# tiny433mhz.net
KiCad netlist of a schematic drawn in EAGLE
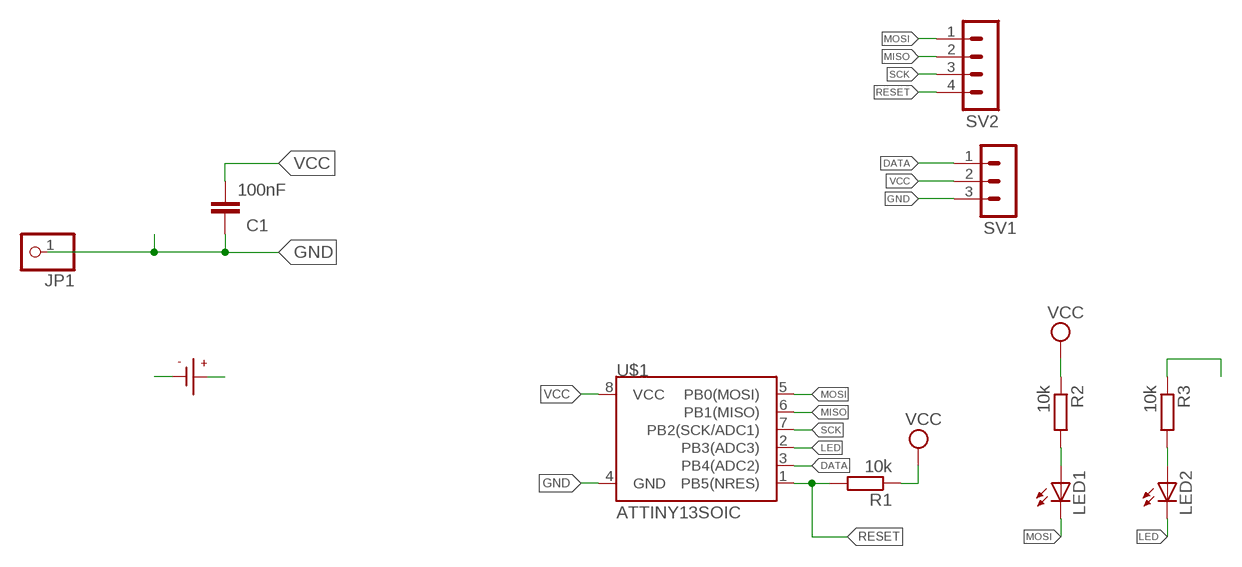
[diagram p0: schematic, sheet 1]

(export (version "E")
  (design (tool "Eeschema 10.0.6"))
  (components
    (comp (ref "C1")
      (value "100nF")
      (footprint "eagle-import:C0805")
      (libsource (lib "eagle-import") (part "C-EUC0805"))
    )
    (comp (ref "JP1")
      (value "PINHD-1X1")
      (footprint "eagle-import:1X01")
      (libsource (lib "eagle-import") (part "PINHD-1X1"))
    )
    (comp (ref "LED1")
      (value "LEDCHIP-LED0805")
      (footprint "eagle-import:CHIP-LED0805")
      (libsource (lib "eagle-import") (part "LEDCHIP-LED0805"))
    )
    (comp (ref "LED2")
      (value "LEDCHIP-LED0805")
      (footprint "eagle-import:CHIP-LED0805")
      (libsource (lib "eagle-import") (part "LEDCHIP-LED0805"))
    )
    (comp (ref "R1")
      (value "10k")
      (footprint "eagle-import:R0805")
      (libsource (lib "eagle-import") (part "R-EU_R0805"))
    )
    (comp (ref "R2")
      (value "10k")
      (footprint "eagle-import:R0805")
      (libsource (lib "eagle-import") (part "R-EU_R0805"))
    )
    (comp (ref "R3")
      (value "10k")
      (footprint "eagle-import:R0805")
      (libsource (lib "eagle-import") (part "R-EU_R0805"))
    )
    (comp (ref "SV1")
      (value "MA03-1")
      (footprint "eagle-import:MA03-1")
      (libsource (lib "eagle-import") (part "MA03-1"))
    )
    (comp (ref "SV2")
      (value "MA04-1")
      (footprint "eagle-import:MA04-1")
      (libsource (lib "eagle-import") (part "MA04-1"))
    )
    (comp (ref "U$1")
      (value "ATTINY13SOIC")
      (footprint "eagle-import:SO08")
      (libsource (lib "eagle-import") (part "ATTINY13SOIC"))
    )
    (comp (ref "U$3")
      (value "CR2032")
      (footprint "eagle-import:CR2032-THT")
      (libsource (lib "eagle-import") (part "CR2032"))
    )
  )
  (nets
    (net (code "1") (name "DATA") (class "Default")
      (node (ref "SV1") (pin "1") (pinfunction "1_1") (pintype "passive"))
      (node (ref "U$1") (pin "3") (pinfunction "PB4(ADC2)_3") (pintype "bidirectional"))
    )
    (net (code "2") (name "GND") (class "Default")
      (node (ref "C1") (pin "1") (pinfunction "1_1") (pintype "passive"))
      (node (ref "JP1") (pin "1") (pinfunction "1_1") (pintype "passive"))
      (node (ref "R3") (pin "1") (pinfunction "1_1") (pintype "passive"))
      (node (ref "SV1") (pin "3") (pinfunction "3_3") (pintype "passive"))
      (node (ref "U$1") (pin "4") (pinfunction "GND_4") (pintype "bidirectional"))
      (node (ref "U$3") (pin "-") (pinfunction "-_-") (pintype "bidirectional"))
    )
    (net (code "3") (name "LED") (class "Default")
      (node (ref "LED2") (pin "C") (pinfunction "C_C") (pintype "passive"))
      (node (ref "U$1") (pin "2") (pinfunction "PB3(ADC3)_2") (pintype "bidirectional"))
    )
    (net (code "4") (name "MISO") (class "Default")
      (node (ref "SV2") (pin "2") (pinfunction "2_2") (pintype "passive"))
      (node (ref "U$1") (pin "6") (pinfunction "PB1(MISO)_6") (pintype "bidirectional"))
    )
    (net (code "5") (name "MOSI") (class "Default")
      (node (ref "LED1") (pin "C") (pinfunction "C_C") (pintype "passive"))
      (node (ref "SV2") (pin "1") (pinfunction "1_1") (pintype "passive"))
      (node (ref "U$1") (pin "5") (pinfunction "PB0(MOSI)_5") (pintype "bidirectional"))
    )
    (net (code "6") (name "Net-(LED1-PadA)") (class "Default")
      (node (ref "LED1") (pin "A") (pinfunction "A_A") (pintype "passive"))
      (node (ref "R2") (pin "2") (pinfunction "2_2") (pintype "passive"))
    )
    (net (code "7") (name "Net-(LED2-PadA)") (class "Default")
      (node (ref "LED2") (pin "A") (pinfunction "A_A") (pintype "passive"))
      (node (ref "R3") (pin "2") (pinfunction "2_2") (pintype "passive"))
    )
    (net (code "8") (name "RESET") (class "Default")
      (node (ref "R1") (pin "2") (pinfunction "2_2") (pintype "passive"))
      (node (ref "SV2") (pin "4") (pinfunction "4_4") (pintype "passive"))
      (node (ref "U$1") (pin "1") (pinfunction "PB5(NRES)_1") (pintype "bidirectional"))
    )
    (net (code "9") (name "SCK") (class "Default")
      (node (ref "SV2") (pin "3") (pinfunction "3_3") (pintype "passive"))
      (node (ref "U$1") (pin "7") (pinfunction "PB2(SCK/ADC1)_7") (pintype "bidirectional"))
    )
    (net (code "10") (name "VCC") (class "Default")
      (node (ref "C1") (pin "2") (pinfunction "2_2") (pintype "passive"))
      (node (ref "R1") (pin "1") (pinfunction "1_1") (pintype "passive"))
      (node (ref "R2") (pin "1") (pinfunction "1_1") (pintype "passive"))
      (node (ref "SV1") (pin "2") (pinfunction "2_2") (pintype "passive"))
      (node (ref "U$1") (pin "8") (pinfunction "VCC_8") (pintype "bidirectional"))
      (node (ref "U$3") (pin "+") (pinfunction "+_+") (pintype "bidirectional"))
    )
  )
)
